# project-tsc.net
KiCad netlist of a schematic drawn in EAGLE
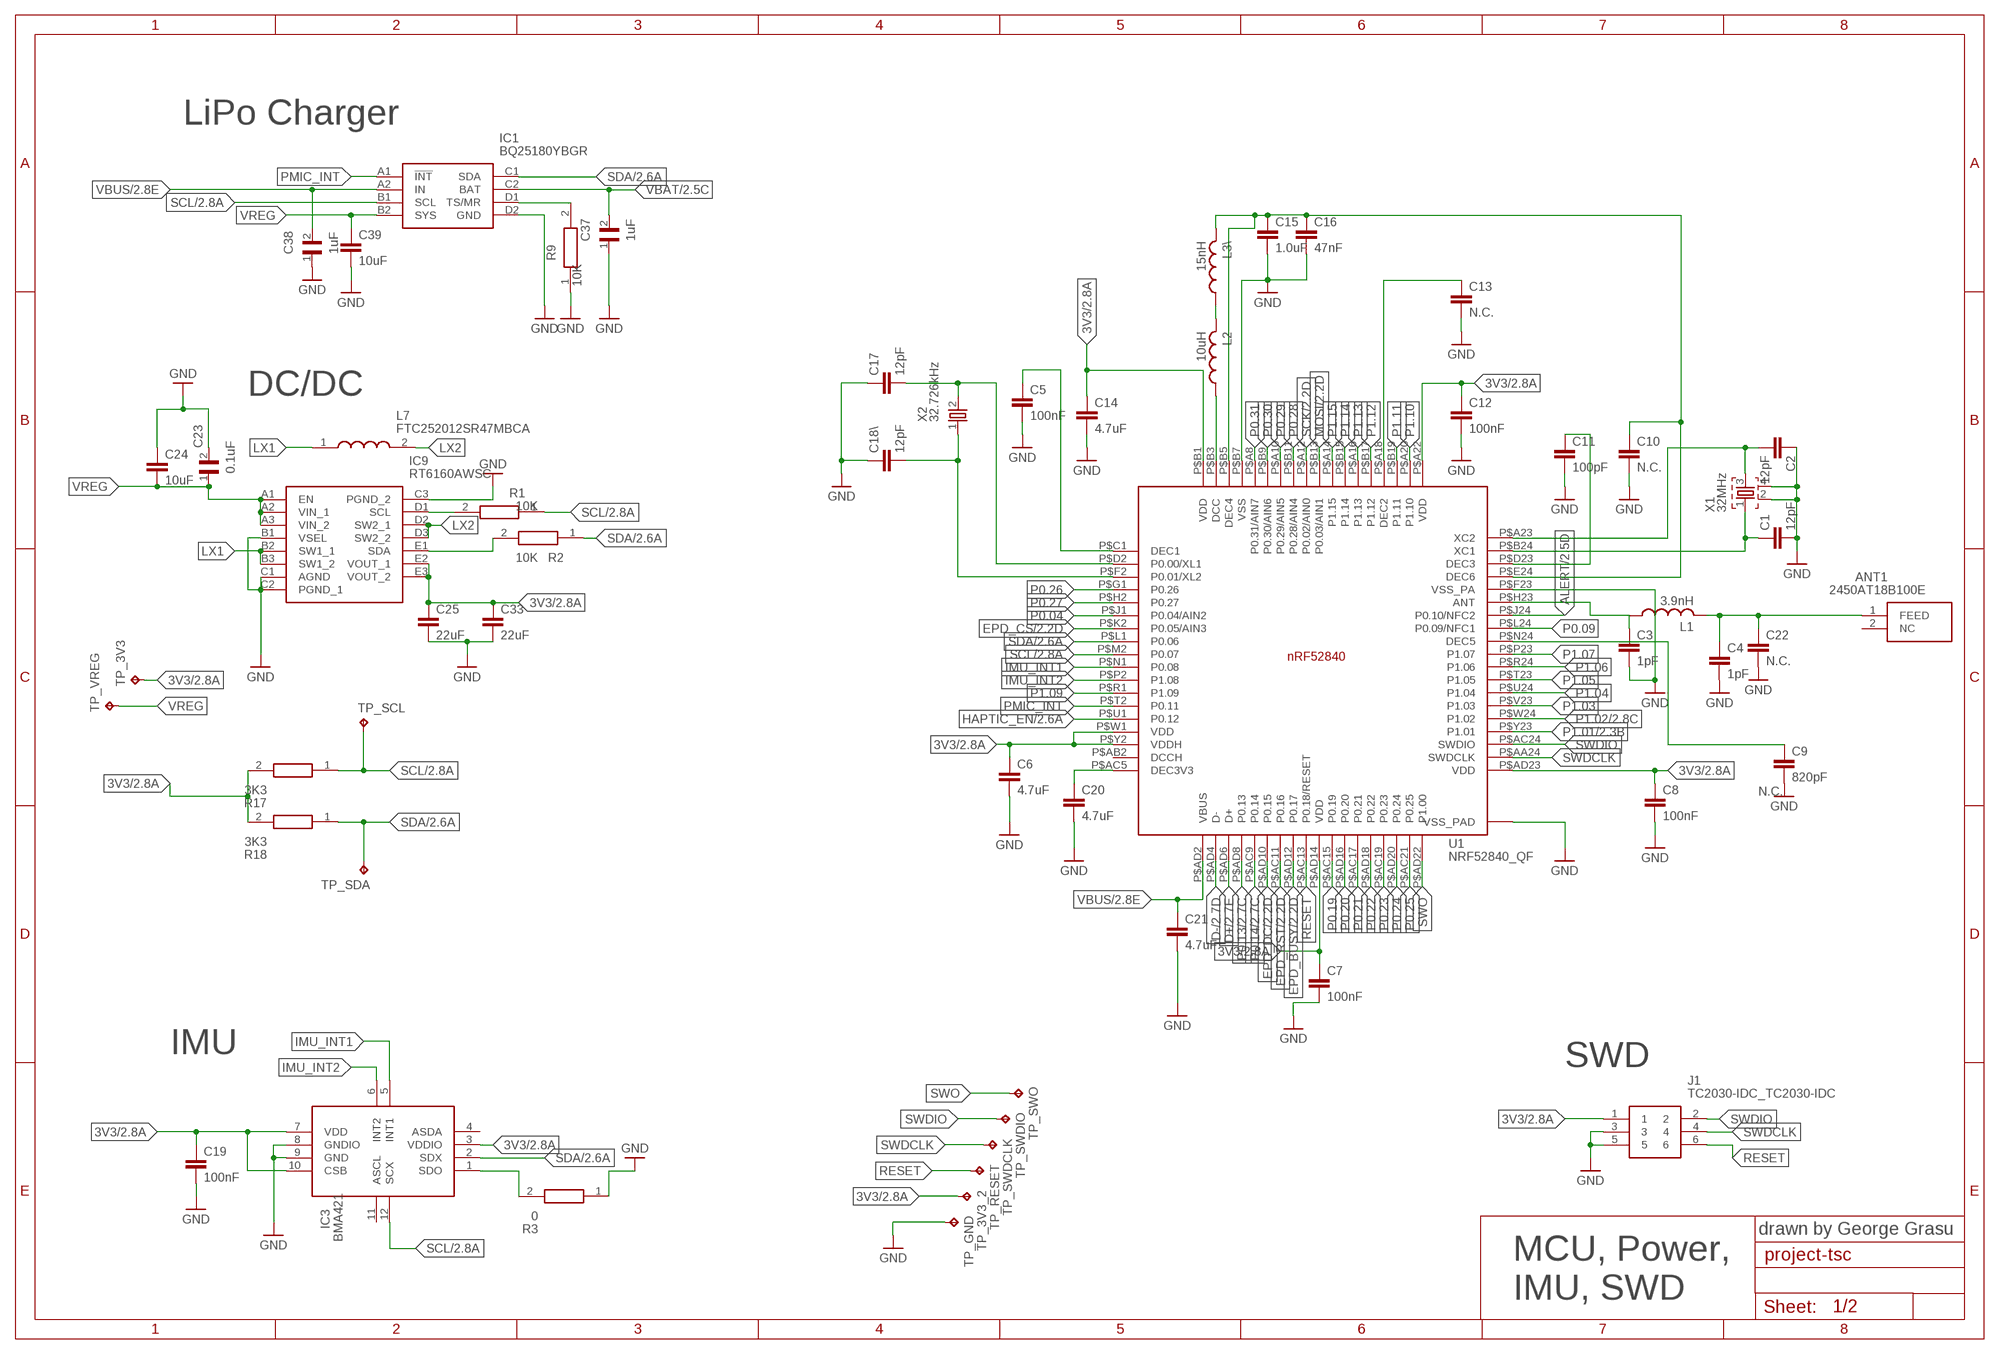
[diagram p0: schematic, sheet 1]
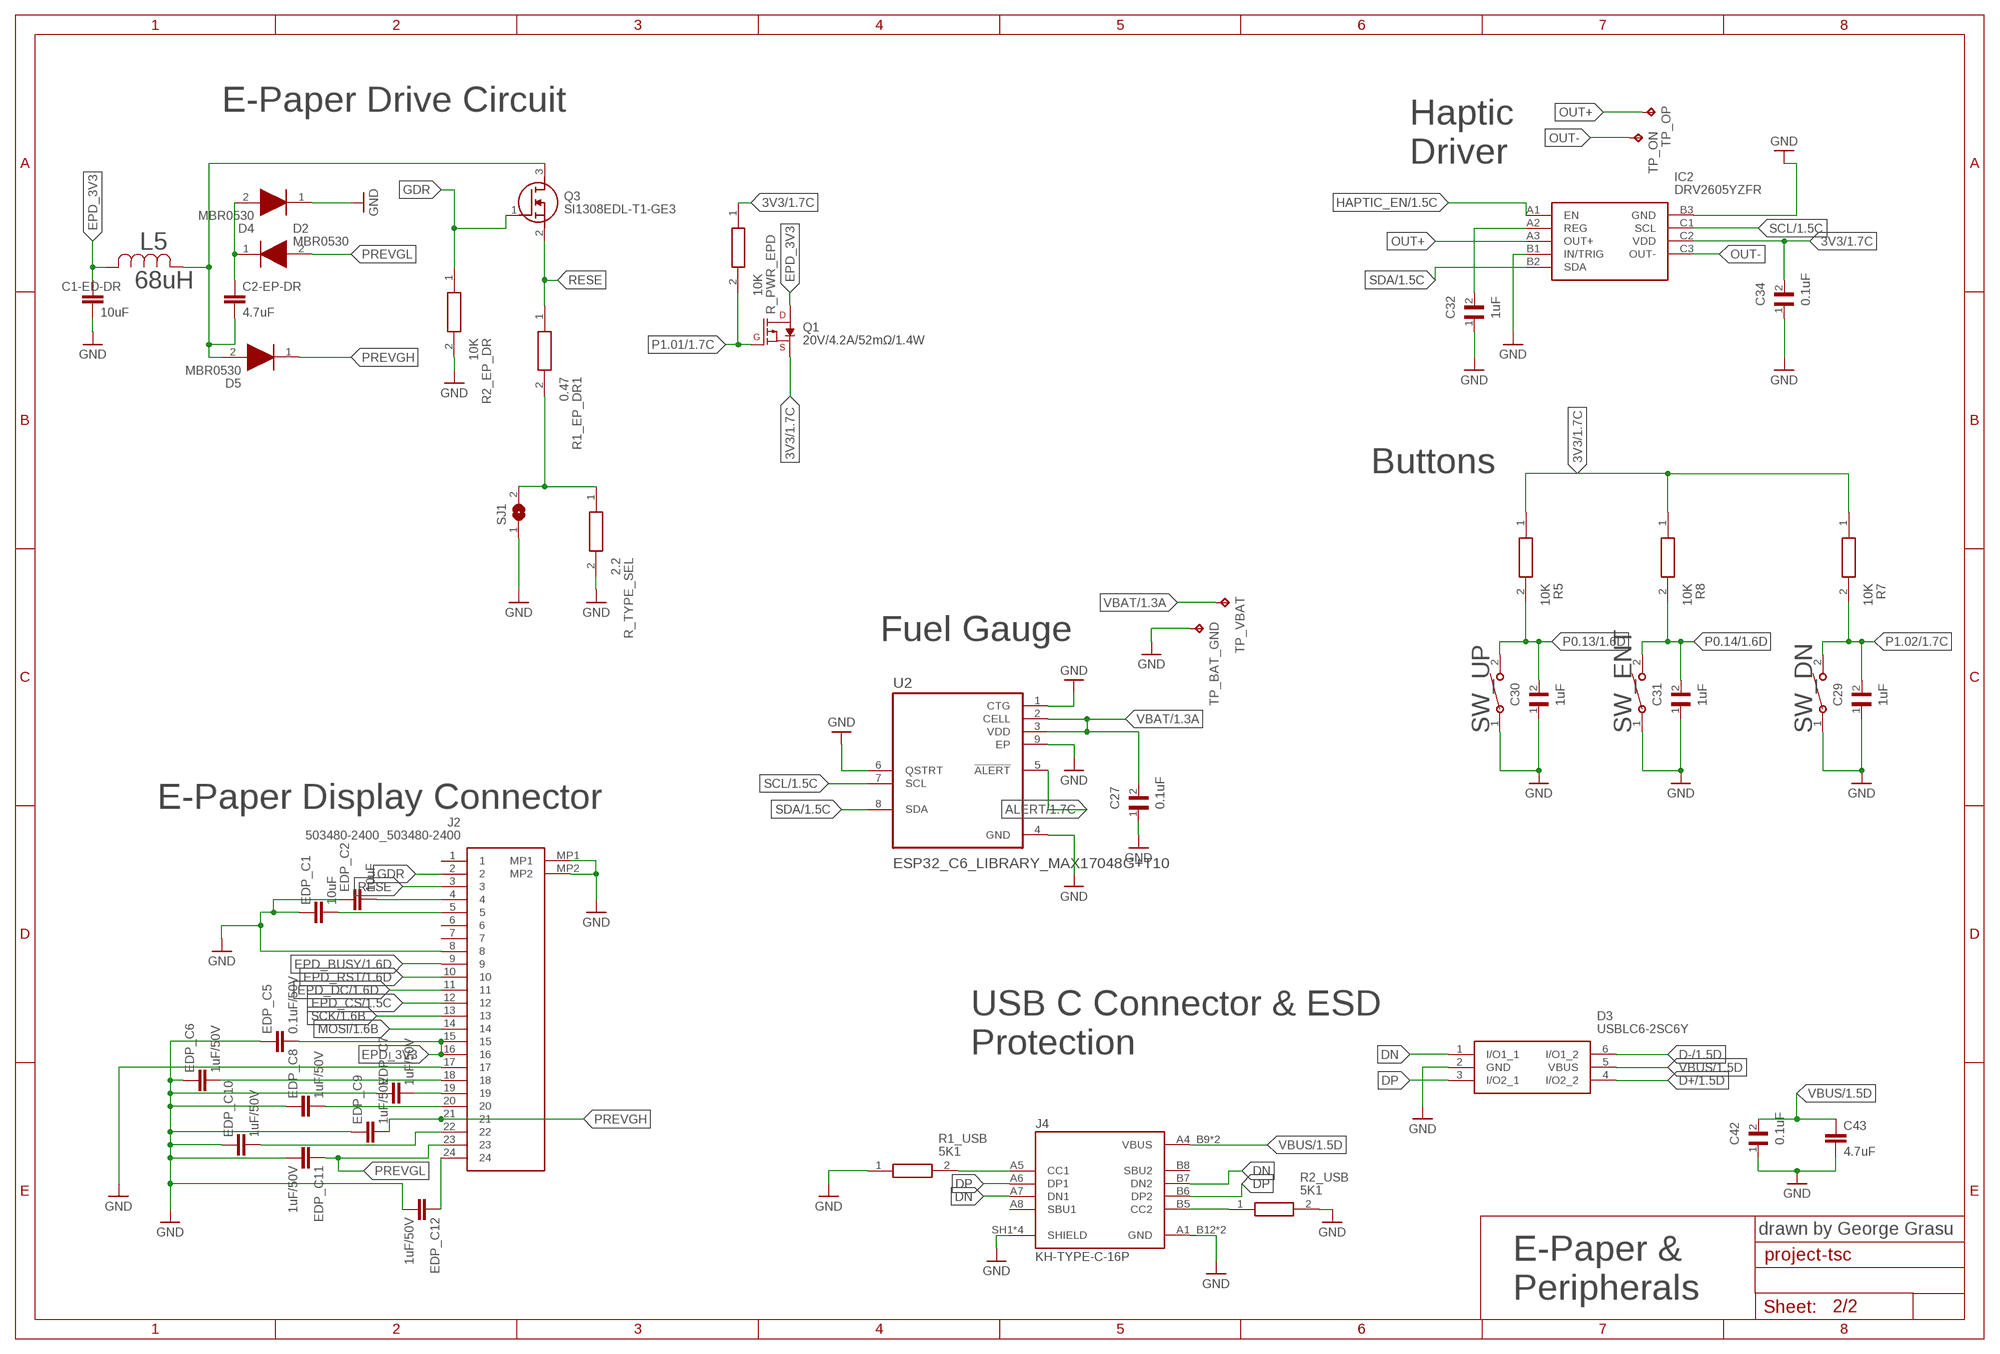
[diagram p1: schematic, sheet 2]

(export (version "E")
  (design (tool "Eeschema 10.0.6"))
  (components
    (comp (ref "ANT1")
      (value "2450AT18B100E")
      (footprint "eagle-import:2450AT18B100E_ANTC3216X140N")
      (fields (field (name "MOUSER_PART_NUMBER") "609-2450AT18B100E"))
      (libsource (lib "eagle-import") (part "2450AT18B100E_2450AT18B100E"))
    )
    (comp (ref "C1")
      (value "12pF")
      (footprint "eagle-import:NORDIC_NRF_3_RESC0201_L")
      (libsource (lib "eagle-import") (part "NORDIC_NRF_3_CAPACITOR_0201_L"))
    )
    (comp (ref "C2")
      (value "12pF")
      (footprint "eagle-import:NORDIC_NRF_3_RESC0201_L")
      (libsource (lib "eagle-import") (part "NORDIC_NRF_3_CAPACITOR_0201_L"))
    )
    (comp (ref "C3")
      (value "1pF")
      (footprint "eagle-import:NORDIC_NRF_3_RESC0201_N")
      (libsource (lib "eagle-import") (part "NORDIC_NRF_3_CAPACITOR_0201_N"))
    )
    (comp (ref "C4")
      (value "1pF")
      (footprint "eagle-import:NORDIC_NRF_3_RESC0201_N")
      (libsource (lib "eagle-import") (part "NORDIC_NRF_3_CAPACITOR_0201_N"))
    )
    (comp (ref "C5")
      (value "100nF")
      (footprint "eagle-import:NORDIC_NRF_3_RESC0201_L")
      (libsource (lib "eagle-import") (part "NORDIC_NRF_3_CAPACITOR_0201_L"))
    )
    (comp (ref "C6")
      (value "4.7uF")
      (footprint "eagle-import:NORDIC_NRF_3_RESC0402_N")
      (libsource (lib "eagle-import") (part "NORDIC_NRF_3_CAPACITOR_0402_N"))
    )
    (comp (ref "C7")
      (value "100nF")
      (footprint "eagle-import:NORDIC_NRF_3_RESC0201_N")
      (libsource (lib "eagle-import") (part "NORDIC_NRF_3_CAPACITOR_0201_N"))
    )
    (comp (ref "C8")
      (value "100nF")
      (footprint "eagle-import:NORDIC_NRF_3_RESC0201_N")
      (libsource (lib "eagle-import") (part "NORDIC_NRF_3_CAPACITOR_0201_N"))
    )
    (comp (ref "C9")
      (value "820pF")
      (footprint "eagle-import:NORDIC_NRF_3_RESC0201_N")
      (libsource (lib "eagle-import") (part "NORDIC_NRF_3_CAPACITOR_0201_N"))
    )
    (comp (ref "C10")
      (value "N.C.")
      (footprint "eagle-import:NORDIC_NRF_3_RESC0201_L")
      (libsource (lib "eagle-import") (part "NORDIC_NRF_3_CAPACITOR_0201_L"))
    )
    (comp (ref "C11")
      (value "100pF")
      (footprint "eagle-import:NORDIC_NRF_3_RESC0201_L")
      (libsource (lib "eagle-import") (part "NORDIC_NRF_3_CAPACITOR_0201_L"))
    )
    (comp (ref "C12")
      (value "100nF")
      (footprint "eagle-import:NORDIC_NRF_3_RESC0201_L")
      (libsource (lib "eagle-import") (part "NORDIC_NRF_3_CAPACITOR_0201_L"))
    )
    (comp (ref "C13")
      (value "N.C.")
      (footprint "eagle-import:NORDIC_NRF_3_RESC0201_L")
      (libsource (lib "eagle-import") (part "NORDIC_NRF_3_CAPACITOR_0201_L"))
    )
    (comp (ref "C14")
      (value "4.7uF")
      (footprint "eagle-import:NORDIC_NRF_3_RESC0201_L")
      (libsource (lib "eagle-import") (part "NORDIC_NRF_3_CAPACITOR_0201_L"))
    )
    (comp (ref "C15")
      (value "1.0uF")
      (footprint "eagle-import:NORDIC_NRF_3_RESC0201_L")
      (libsource (lib "eagle-import") (part "NORDIC_NRF_3_CAPACITOR_0201_L"))
    )
    (comp (ref "C16")
      (value "47nF")
      (footprint "eagle-import:NORDIC_NRF_3_RESC0201_L")
      (libsource (lib "eagle-import") (part "NORDIC_NRF_3_CAPACITOR_0201_L"))
    )
    (comp (ref "C17")
      (value "12pF")
      (footprint "eagle-import:NORDIC_NRF_3_RESC0201_L")
      (libsource (lib "eagle-import") (part "NORDIC_NRF_3_CAPACITOR_0201_L"))
    )
    (comp (ref "C18\\")
      (value "12pF")
      (footprint "eagle-import:NORDIC_NRF_3_RESC0201_L")
      (libsource (lib "eagle-import") (part "NORDIC_NRF_3_CAPACITOR_0201_L"))
    )
    (comp (ref "C19")
      (value "100nF")
      (footprint "eagle-import:NORDIC_NRF_3_RESC0201_L")
      (libsource (lib "eagle-import") (part "NORDIC_NRF_3_CAPACITOR_0201_L"))
    )
    (comp (ref "C20")
      (value "4.7uF")
      (footprint "eagle-import:NORDIC_NRF_3_RESC0402_N")
      (libsource (lib "eagle-import") (part "NORDIC_NRF_3_CAPACITOR_0402_N"))
    )
    (comp (ref "C21")
      (value "4.7uF")
      (footprint "eagle-import:NORDIC_NRF_3_RESC0402_N")
      (libsource (lib "eagle-import") (part "NORDIC_NRF_3_CAPACITOR_0402_N"))
    )
    (comp (ref "C22")
      (value "N.C.")
      (footprint "eagle-import:NORDIC_NRF_3_RESC0201_N")
      (libsource (lib "eagle-import") (part "NORDIC_NRF_3_CAPACITOR_0201_N"))
    )
    (comp (ref "C23")
      (value "0.1uF")
      (footprint "eagle-import:GRM011R60J152KE01L_2_CAPC0201X13N")
      (fields (field (name "MF") "Murata") (field (name "MP") "GRM011R60J152KE01L"))
      (libsource (lib "eagle-import") (part "GRM011R60J152KE01L_2_GRM011R60J152KE01L"))
    )
    (comp (ref "C24")
      (value "10uF")
      (footprint "eagle-import:NORDIC_NRF_3_RESC0201_L")
      (libsource (lib "eagle-import") (part "NORDIC_NRF_3_CAPACITOR_0201_L"))
    )
    (comp (ref "C25")
      (value "22uF")
      (footprint "eagle-import:NORDIC_NRF_3_RESC0201_L")
      (libsource (lib "eagle-import") (part "NORDIC_NRF_3_CAPACITOR_0201_L"))
    )
    (comp (ref "C33")
      (value "22uF")
      (footprint "eagle-import:NORDIC_NRF_3_RESC0201_L")
      (libsource (lib "eagle-import") (part "NORDIC_NRF_3_CAPACITOR_0201_L"))
    )
    (comp (ref "C37")
      (value "1uF")
      (footprint "eagle-import:GRM011R60J152KE01L_2_CAPC0201X13N")
      (fields (field (name "MF") "Murata") (field (name "MP") "GRM011R60J152KE01L"))
      (libsource (lib "eagle-import") (part "GRM011R60J152KE01L_2_GRM011R60J152KE01L"))
    )
    (comp (ref "C38")
      (value "1uF")
      (footprint "eagle-import:GRM011R60J152KE01L_2_CAPC0201X13N")
      (fields (field (name "MF") "Murata") (field (name "MP") "GRM011R60J152KE01L"))
      (libsource (lib "eagle-import") (part "GRM011R60J152KE01L_2_GRM011R60J152KE01L"))
    )
    (comp (ref "C39")
      (value "10uF")
      (footprint "eagle-import:NORDIC_NRF_3_RESC0201_L")
      (libsource (lib "eagle-import") (part "NORDIC_NRF_3_CAPACITOR_0201_L"))
    )
    (comp (ref "IC1")
      (value "BQ25180YBGR")
      (footprint "eagle-import:BQ25180YBGR_BGA8C40P2X4_100X155X50")
      (fields (field (name "MOUSER_PART_NUMBER") "595-BQ25180YBGR"))
      (libsource (lib "eagle-import") (part "BQ25180YBGR_BQ25180YBGR"))
    )
    (comp (ref "IC3")
      (value "BMA421")
      (footprint "eagle-import:BMA423_BMA423")
      (fields (field (name "ARROW_PART_NUMBER") "BMA423") (field (name "MOUSER_PART_NUMBER") "262-BMA423"))
      (libsource (lib "eagle-import") (part "BMA423_BMA423"))
    )
    (comp (ref "IC9")
      (value "RT6160AWSC")
      (footprint "eagle-import:RT6160AWSC_BGA15C40P3X5_140X230X60")
      (fields (field (name "MOUSER_PART_NUMBER") "835-RT6160AWSC"))
      (libsource (lib "eagle-import") (part "RT6160AWSC_RT6160AWSC"))
    )
    (comp (ref "J1")
      (value "TC2030-IDC_TC2030-IDC")
      (footprint "eagle-import:TC2030-IDC_TC2030IDC")
      (fields (field (name "MANUFACTURER_PART_NUMBER") "TC2030-IDC"))
      (libsource (lib "eagle-import") (part "TC2030-IDC_TC2030-IDC"))
    )
    (comp (ref "L1")
      (value "3.9nH")
      (footprint "eagle-import:NORDIC_NRF_2_RESC0402_L")
      (libsource (lib "eagle-import") (part "NORDIC_NRF_2_INDUCTOR_0402_L"))
    )
    (comp (ref "L2")
      (value "10uH")
      (footprint "eagle-import:NORDIC_NRF_2_RESC0402_L")
      (libsource (lib "eagle-import") (part "NORDIC_NRF_2_INDUCTOR_0402_L"))
    )
    (comp (ref "L3\\")
      (value "15nH")
      (footprint "eagle-import:NORDIC_NRF_2_RESC0402_L")
      (libsource (lib "eagle-import") (part "NORDIC_NRF_2_INDUCTOR_0402_L"))
    )
    (comp (ref "L7")
      (value "FTC252012SR47MBCA")
      (footprint "eagle-import:MLP2016SR47MT0S1_INDC2016X100N")
      (libsource (lib "eagle-import") (part "MLP2016SR47MT0S1_FTC252012SR47MBCA"))
    )
    (comp (ref "R1")
      (value "10K")
      (footprint "eagle-import:CPF0201D7K68C1_0201")
      (libsource (lib "eagle-import") (part "CPF0201D7K68C1_CPF0201D7K68C1"))
    )
    (comp (ref "R2")
      (value "10K")
      (footprint "eagle-import:CPF0201D7K68C1_0201")
      (libsource (lib "eagle-import") (part "CPF0201D7K68C1_CPF0201D7K68C1"))
    )
    (comp (ref "R3")
      (value "0")
      (footprint "eagle-import:CPF0201D7K68C1_0201")
      (libsource (lib "eagle-import") (part "CPF0201D7K68C1_CPF0201D7K68C1"))
    )
    (comp (ref "R9")
      (value "10K")
      (footprint "eagle-import:CPF0201D7K68C1_0201")
      (libsource (lib "eagle-import") (part "CPF0201D7K68C1_CPF0201D7K68C1"))
    )
    (comp (ref "R17")
      (value "3K3")
      (footprint "eagle-import:CPF0201D7K68C1_0201")
      (libsource (lib "eagle-import") (part "CPF0201D7K68C1_CPF0201D7K68C1"))
    )
    (comp (ref "R18")
      (value "3K3")
      (footprint "eagle-import:CPF0201D7K68C1_0201")
      (libsource (lib "eagle-import") (part "CPF0201D7K68C1_CPF0201D7K68C1"))
    )
    (comp (ref "TP_3V3")
      (value "HECTOR_WATCH_1_TPTP20R")
      (footprint "eagle-import:HECTOR_WATCH_1_TP20R")
      (libsource (lib "eagle-import") (part "HECTOR_WATCH_1_TPTP20R"))
    )
    (comp (ref "TP_3V3_2")
      (value "HECTOR_WATCH_1_TPTP20R")
      (footprint "eagle-import:HECTOR_WATCH_1_TP20R")
      (libsource (lib "eagle-import") (part "HECTOR_WATCH_1_TPTP20R"))
    )
    (comp (ref "TP_GND")
      (value "HECTOR_WATCH_1_TPTP20R")
      (footprint "eagle-import:HECTOR_WATCH_1_TP20R")
      (libsource (lib "eagle-import") (part "HECTOR_WATCH_1_TPTP20R"))
    )
    (comp (ref "TP_RESET")
      (value "HECTOR_WATCH_1_TPTP20R")
      (footprint "eagle-import:HECTOR_WATCH_1_TP20R")
      (libsource (lib "eagle-import") (part "HECTOR_WATCH_1_TPTP20R"))
    )
    (comp (ref "TP_SCL")
      (value "HECTOR_WATCH_1_TPTP20R")
      (footprint "eagle-import:HECTOR_WATCH_1_TP20R")
      (libsource (lib "eagle-import") (part "HECTOR_WATCH_1_TPTP20R"))
    )
    (comp (ref "TP_SDA")
      (value "HECTOR_WATCH_1_TPTP20R")
      (footprint "eagle-import:HECTOR_WATCH_1_TP20R")
      (libsource (lib "eagle-import") (part "HECTOR_WATCH_1_TPTP20R"))
    )
    (comp (ref "TP_SWDCLK")
      (value "HECTOR_WATCH_1_TPTP20R")
      (footprint "eagle-import:HECTOR_WATCH_1_TP20R")
      (libsource (lib "eagle-import") (part "HECTOR_WATCH_1_TPTP20R"))
    )
    (comp (ref "TP_SWDIO")
      (value "HECTOR_WATCH_1_TPTP20R")
      (footprint "eagle-import:HECTOR_WATCH_1_TP20R")
      (libsource (lib "eagle-import") (part "HECTOR_WATCH_1_TPTP20R"))
    )
    (comp (ref "TP_SWO")
      (value "HECTOR_WATCH_1_TPTP20R")
      (footprint "eagle-import:HECTOR_WATCH_1_TP20R")
      (libsource (lib "eagle-import") (part "HECTOR_WATCH_1_TPTP20R"))
    )
    (comp (ref "TP_VREG")
      (value "HECTOR_WATCH_1_TPTP20R")
      (footprint "eagle-import:HECTOR_WATCH_1_TP20R")
      (libsource (lib "eagle-import") (part "HECTOR_WATCH_1_TPTP20R"))
    )
    (comp (ref "U1")
      (value "NRF52840_QF")
      (footprint "eagle-import:NORDIC_NRF_4_AQFN50P700X700X85_HS-74N")
      (libsource (lib "eagle-import") (part "NORDIC_NRF_4_NRF52840_QF"))
    )
    (comp (ref "X1")
      (value "32MHz")
      (footprint "eagle-import:NORDIC_NRF_BT-XTAL_2016_N")
      (libsource (lib "eagle-import") (part "NORDIC_NRF_XTAL_32MHZ"))
    )
    (comp (ref "X2")
      (value "32.726kHz")
      (footprint "eagle-import:NORDIC_NRF_1_XTAL_3215_N")
      (libsource (lib "eagle-import") (part "NORDIC_NRF_1_XTAL_32KHZ"))
    )
    (comp (ref "C1-ED-DR")
      (value "10uF")
      (footprint "eagle-import:NORDIC_NRF_3_RESC0402_N")
      (libsource (lib "eagle-import") (part "NORDIC_NRF_3_CAPACITOR_0402_N"))
    )
    (comp (ref "C2-EP-DR")
      (value "4.7uF")
      (footprint "eagle-import:NORDIC_NRF_3_RESC0402_N")
      (libsource (lib "eagle-import") (part "NORDIC_NRF_3_CAPACITOR_0402_N"))
    )
    (comp (ref "C27")
      (value "0.1uF")
      (footprint "eagle-import:GRM011R60J152KE01L_2_CAPC0201X13N")
      (fields (field (name "MF") "Murata") (field (name "MP") "GRM011R60J152KE01L"))
      (libsource (lib "eagle-import") (part "GRM011R60J152KE01L_2_GRM011R60J152KE01L"))
    )
    (comp (ref "C29")
      (value "1uF")
      (footprint "eagle-import:GRM011R60J152KE01L_2_CAPC0201X13N")
      (fields (field (name "MF") "Murata") (field (name "MP") "GRM011R60J152KE01L"))
      (libsource (lib "eagle-import") (part "GRM011R60J152KE01L_2_GRM011R60J152KE01L"))
    )
    (comp (ref "C30")
      (value "1uF")
      (footprint "eagle-import:GRM011R60J152KE01L_2_CAPC0201X13N")
      (fields (field (name "MF") "Murata") (field (name "MP") "GRM011R60J152KE01L"))
      (libsource (lib "eagle-import") (part "GRM011R60J152KE01L_2_GRM011R60J152KE01L"))
    )
    (comp (ref "C31")
      (value "1uF")
      (footprint "eagle-import:GRM011R60J152KE01L_2_CAPC0201X13N")
      (fields (field (name "MF") "Murata") (field (name "MP") "GRM011R60J152KE01L"))
      (libsource (lib "eagle-import") (part "GRM011R60J152KE01L_2_GRM011R60J152KE01L"))
    )
    (comp (ref "C32")
      (value "1uF")
      (footprint "eagle-import:GRM011R60J152KE01L_2_CAPC0201X13N")
      (fields (field (name "MF") "Murata") (field (name "MP") "GRM011R60J152KE01L"))
      (libsource (lib "eagle-import") (part "GRM011R60J152KE01L_2_GRM011R60J152KE01L"))
    )
    (comp (ref "C34")
      (value "0.1uF")
      (footprint "eagle-import:GRM011R60J152KE01L_2_CAPC0201X13N")
      (fields (field (name "MF") "Murata") (field (name "MP") "GRM011R60J152KE01L"))
      (libsource (lib "eagle-import") (part "GRM011R60J152KE01L_2_GRM011R60J152KE01L"))
    )
    (comp (ref "C42")
      (value "0.1uF")
      (footprint "eagle-import:GRM011R60J152KE01L_2_CAPC0201X13N")
      (fields (field (name "MF") "Murata") (field (name "MP") "GRM011R60J152KE01L"))
      (libsource (lib "eagle-import") (part "GRM011R60J152KE01L_2_GRM011R60J152KE01L"))
    )
    (comp (ref "C43")
      (value "4.7uF")
      (footprint "eagle-import:NORDIC_NRF_3_RESC0201_L")
      (libsource (lib "eagle-import") (part "NORDIC_NRF_3_CAPACITOR_0201_L"))
    )
    (comp (ref "D2")
      (value "MBR0530")
      (footprint "eagle-import:ESP32_C6_LIBRARY_5_SOD3716X135N")
      (fields (field (name "MF") "ON Semiconductor"))
      (libsource (lib "eagle-import") (part "ESP32_C6_LIBRARY_5_MBR0530"))
    )
    (comp (ref "D3")
      (value "USBLC6-2SC6Y")
      (footprint "eagle-import:ESP32_C6_LIBRARY_3_SOT95P280X145-6N")
      (fields (field (name "MF") "STMicroelectronics"))
      (libsource (lib "eagle-import") (part "ESP32_C6_LIBRARY_3_USBLC6-2SC6Y"))
    )
    (comp (ref "D4")
      (value "MBR0530")
      (footprint "eagle-import:ESP32_C6_LIBRARY_5_SOD3716X135N")
      (fields (field (name "MF") "ON Semiconductor"))
      (libsource (lib "eagle-import") (part "ESP32_C6_LIBRARY_5_MBR0530"))
    )
    (comp (ref "D5")
      (value "MBR0530")
      (footprint "eagle-import:ESP32_C6_LIBRARY_5_SOD3716X135N")
      (fields (field (name "MF") "ON Semiconductor"))
      (libsource (lib "eagle-import") (part "ESP32_C6_LIBRARY_5_MBR0530"))
    )
    (comp (ref "EDP_C1")
      (value "10uF")
      (footprint "eagle-import:NORDIC_NRF_3_RESC0201_L")
      (libsource (lib "eagle-import") (part "NORDIC_NRF_3_CAPACITOR_0201_L"))
    )
    (comp (ref "EDP_C2")
      (value "10uF")
      (footprint "eagle-import:NORDIC_NRF_3_RESC0201_L")
      (libsource (lib "eagle-import") (part "NORDIC_NRF_3_CAPACITOR_0201_L"))
    )
    (comp (ref "EDP_C5")
      (value "0.1uF/50V")
      (footprint "eagle-import:NORDIC_NRF_3_RESC0201_L")
      (libsource (lib "eagle-import") (part "NORDIC_NRF_3_CAPACITOR_0201_L"))
    )
    (comp (ref "EDP_C6")
      (value "1uF/50V")
      (footprint "eagle-import:NORDIC_NRF_3_RESC0201_L")
      (libsource (lib "eagle-import") (part "NORDIC_NRF_3_CAPACITOR_0201_L"))
    )
    (comp (ref "EDP_C7")
      (value "1uF/50V")
      (footprint "eagle-import:NORDIC_NRF_3_RESC0201_L")
      (libsource (lib "eagle-import") (part "NORDIC_NRF_3_CAPACITOR_0201_L"))
    )
    (comp (ref "EDP_C8")
      (value "1uF/50V")
      (footprint "eagle-import:NORDIC_NRF_3_RESC0201_L")
      (libsource (lib "eagle-import") (part "NORDIC_NRF_3_CAPACITOR_0201_L"))
    )
    (comp (ref "EDP_C9")
      (value "1uF/50V")
      (footprint "eagle-import:NORDIC_NRF_3_RESC0201_L")
      (libsource (lib "eagle-import") (part "NORDIC_NRF_3_CAPACITOR_0201_L"))
    )
    (comp (ref "EDP_C10")
      (value "1uF/50V")
      (footprint "eagle-import:NORDIC_NRF_3_RESC0201_L")
      (libsource (lib "eagle-import") (part "NORDIC_NRF_3_CAPACITOR_0201_L"))
    )
    (comp (ref "EDP_C11")
      (value "1uF/50V")
      (footprint "eagle-import:NORDIC_NRF_3_RESC0201_L")
      (libsource (lib "eagle-import") (part "NORDIC_NRF_3_CAPACITOR_0201_L"))
    )
    (comp (ref "EDP_C12")
      (value "1uF/50V")
      (footprint "eagle-import:NORDIC_NRF_3_RESC0201_L")
      (libsource (lib "eagle-import") (part "NORDIC_NRF_3_CAPACITOR_0201_L"))
    )
    (comp (ref "IC2")
      (value "DRV2605YZFR")
      (footprint "eagle-import:DRV2605YZFR_BGA9C50P3X3_144X144X62")
      (libsource (lib "eagle-import") (part "DRV2605YZFR_DRV2605YZFR"))
    )
    (comp (ref "J2")
      (value "503480-2400_503480-2400")
      (footprint "eagle-import:503480-2400_5034802400")
      (fields
        (field (name "MANUFACTURER_PART_NUMBER") "503480-2400")
        (field (name "MOUSER_PART_NUMBER") "538-503480-2400")
      )
      (libsource (lib "eagle-import") (part "503480-2400_503480-2400"))
    )
    (comp (ref "J4")
      (value "KH-TYPE-C-16P")
      (footprint "eagle-import:KH-TYPE-C-16P_KINGHELM_KH-TYPE-C-16P")
      (fields (field (name "MF") "kinghelm"))
      (libsource (lib "eagle-import") (part "KH-TYPE-C-16P_KH-TYPE-C-16P"))
    )
    (comp (ref "L5")
      (value "68uH")
      (footprint "eagle-import:ESP32_C6_LIBRARY_2_IND_4828-WE-TPC_WRE")
      (fields
        (field (name "MANUFACTURER_PART_NUMBER") "744043680")
        (field (name "COPYRIGHT") "Copyright (C) 2024 Ultra Librarian. All rights reserved.")
      )
      (libsource (lib "eagle-import") (part "ESP32_C6_LIBRARY_2_744043680IND_4828-WE-TPC_WRE"))
    )
    (comp (ref "Q1")
      (value "20V/4.2A/52mΩ/1.4W")
      (footprint "eagle-import:ESP32_C6_LIBRARY_4_ESP32_C6_LIBRARY_4_ESP32_C6_LIBRARY_4_ESP32_C6_LIBRARY_4_ESP32_WROVER_SPARKFUN-DISCRETESEMI_SOT23-3")
      (libsource (lib "eagle-import") (part "ESP32_C6_LIBRARY_4_ESP32_WROVER_SPARKFUN-DISCRETESEMI_MOSFET_PCH-DMG2305UX-7"))
    )
    (comp (ref "Q3")
      (value "SI1308EDL-T1-GE3")
      (footprint "eagle-import:ESP32_C6_LIBRARY_6_SOT65P210X110-3N")
      (fields (field (name "MF") "Vishay Siliconix"))
      (libsource (lib "eagle-import") (part "ESP32_C6_LIBRARY_6_SI1308EDL-T1-GE3"))
    )
    (comp (ref "R1_EP_DR1")
      (value "0.47")
      (footprint "eagle-import:CPF0201D7K68C1_0201")
      (libsource (lib "eagle-import") (part "CPF0201D7K68C1_CPF0201D7K68C1"))
    )
    (comp (ref "R1_USB")
      (value "5K1")
      (footprint "eagle-import:CPF0201D7K68C1_0201")
      (libsource (lib "eagle-import") (part "CPF0201D7K68C1_CPF0201D7K68C1"))
    )
    (comp (ref "R2_EP_DR")
      (value "10K")
      (footprint "eagle-import:CPF0201D7K68C1_0201")
      (libsource (lib "eagle-import") (part "CPF0201D7K68C1_CPF0201D7K68C1"))
    )
    (comp (ref "R2_USB")
      (value "5K1")
      (footprint "eagle-import:CPF0201D7K68C1_0201")
      (libsource (lib "eagle-import") (part "CPF0201D7K68C1_CPF0201D7K68C1"))
    )
    (comp (ref "R5")
      (value "10K")
      (footprint "eagle-import:CPF0201D7K68C1_0201")
      (libsource (lib "eagle-import") (part "CPF0201D7K68C1_CPF0201D7K68C1"))
    )
    (comp (ref "R7")
      (value "10K")
      (footprint "eagle-import:CPF0201D7K68C1_0201")
      (libsource (lib "eagle-import") (part "CPF0201D7K68C1_CPF0201D7K68C1"))
    )
    (comp (ref "R8")
      (value "10K")
      (footprint "eagle-import:CPF0201D7K68C1_0201")
      (libsource (lib "eagle-import") (part "CPF0201D7K68C1_CPF0201D7K68C1"))
    )
    (comp (ref "R_PWR_EPD")
      (value "10K")
      (footprint "eagle-import:CPF0201D7K68C1_0201")
      (libsource (lib "eagle-import") (part "CPF0201D7K68C1_CPF0201D7K68C1"))
    )
    (comp (ref "R_TYPE_SEL")
      (value "2.2")
      (footprint "eagle-import:CPF0201D7K68C1_0201")
      (libsource (lib "eagle-import") (part "CPF0201D7K68C1_CPF0201D7K68C1"))
    )
    (comp (ref "SJ1")
      (value "ESP32_C6_LIBRARY_7_JUMPER_SJ")
      (footprint "eagle-import:ESP32_C6_LIBRARY_7_JUMPER_SJ")
      (libsource (lib "eagle-import") (part "ESP32_C6_LIBRARY_7_JUMPER_SJ"))
    )
    (comp (ref "SW_DN")
      (value "2025-10-22_07-23-44_LIBRARY_EVP-AKE31ASW_EVP-AKE31A_PAN")
      (footprint "eagle-import:2025-10-22_07-23-44_LIBRARY_SW_EVP-AKE31A_PAN")
      (fields
        (field (name "MANUFACTURER_PART_NUMBER") "EVP-AKE31A")
        (field (name "COPYRIGHT") "Copyright (C) 2025 Ultra Librarian. All rights reserved.")
      )
      (libsource (lib "eagle-import") (part "2025-10-22_07-23-44_LIBRARY_EVP-AKE31ASW_EVP-AKE31A_PAN"))
    )
    (comp (ref "SW_ENT")
      (value "2025-10-22_07-23-44_LIBRARY_EVP-AKE31ASW_EVP-AKE31A_PAN")
      (footprint "eagle-import:2025-10-22_07-23-44_LIBRARY_SW_EVP-AKE31A_PAN")
      (fields
        (field (name "MANUFACTURER_PART_NUMBER") "EVP-AKE31A")
        (field (name "COPYRIGHT") "Copyright (C) 2025 Ultra Librarian. All rights reserved.")
      )
      (libsource (lib "eagle-import") (part "2025-10-22_07-23-44_LIBRARY_EVP-AKE31ASW_EVP-AKE31A_PAN"))
    )
    (comp (ref "SW_UP")
      (value "2025-10-22_07-23-44_LIBRARY_EVP-AKE31ASW_EVP-AKE31A_PAN")
      (footprint "eagle-import:2025-10-22_07-23-44_LIBRARY_SW_EVP-AKE31A_PAN")
      (fields
        (field (name "MANUFACTURER_PART_NUMBER") "EVP-AKE31A")
        (field (name "COPYRIGHT") "Copyright (C) 2025 Ultra Librarian. All rights reserved.")
      )
      (libsource (lib "eagle-import") (part "2025-10-22_07-23-44_LIBRARY_EVP-AKE31ASW_EVP-AKE31A_PAN"))
    )
    (comp (ref "TP_BAT_GND")
      (value "HECTOR_WATCH_1_TPTP20R")
      (footprint "eagle-import:HECTOR_WATCH_1_TP20R")
      (libsource (lib "eagle-import") (part "HECTOR_WATCH_1_TPTP20R"))
    )
    (comp (ref "TP_ON")
      (value "HECTOR_WATCH_1_TPTP20R")
      (footprint "eagle-import:HECTOR_WATCH_1_TP20R")
      (libsource (lib "eagle-import") (part "HECTOR_WATCH_1_TPTP20R"))
    )
    (comp (ref "TP_OP")
      (value "HECTOR_WATCH_1_TPTP20R")
      (footprint "eagle-import:HECTOR_WATCH_1_TP20R")
      (libsource (lib "eagle-import") (part "HECTOR_WATCH_1_TPTP20R"))
    )
    (comp (ref "TP_VBAT")
      (value "HECTOR_WATCH_1_TPTP20R")
      (footprint "eagle-import:HECTOR_WATCH_1_TP20R")
      (libsource (lib "eagle-import") (part "HECTOR_WATCH_1_TPTP20R"))
    )
    (comp (ref "U2")
      (value "ESP32_C6_LIBRARY_MAX17048G+T10")
      (footprint "eagle-import:ESP32_C6_LIBRARY_SON50P200X200X80-9N")
      (fields (field (name "MF") "Analog Devices") (field (name "MP") "MAX17048G+T10"))
      (libsource (lib "eagle-import") (part "ESP32_C6_LIBRARY_MAX17048G+T10"))
    )
  )
  (nets
    (net (code "1") (name "3V3") (class "Default")
      (node (ref "C12") (pin "1") (pinfunction "1_1") (pintype "passive"))
      (node (ref "C14") (pin "1") (pinfunction "1_1") (pintype "passive"))
      (node (ref "C19") (pin "1") (pinfunction "1_1") (pintype "passive"))
      (node (ref "C25") (pin "1") (pinfunction "1_1") (pintype "passive"))
      (node (ref "C33") (pin "1") (pinfunction "1_1") (pintype "passive"))
      (node (ref "C34") (pin "2") (pinfunction "2_2") (pintype "passive"))
      (node (ref "C6") (pin "1") (pinfunction "1_1") (pintype "passive"))
      (node (ref "C7") (pin "1") (pinfunction "1_1") (pintype "passive"))
      (node (ref "C8") (pin "1") (pinfunction "1_1") (pintype "passive"))
      (node (ref "IC2") (pin "C2") (pinfunction "VDD_C2") (pintype "bidirectional"))
      (node (ref "IC3") (pin "10") (pinfunction "CSB_10") (pintype "bidirectional"))
      (node (ref "IC3") (pin "3") (pinfunction "VDDIO_3") (pintype "bidirectional"))
      (node (ref "IC3") (pin "7") (pinfunction "VDD_7") (pintype "bidirectional"))
      (node (ref "IC9") (pin "E2") (pinfunction "VOUT_1_E2") (pintype "bidirectional"))
      (node (ref "IC9") (pin "E3") (pinfunction "VOUT_2_E3") (pintype "bidirectional"))
      (node (ref "J1") (pin "1") (pinfunction "1_1") (pintype "bidirectional"))
      (node (ref "Q1") (pin "2") (pinfunction "S_2") (pintype "bidirectional"))
      (node (ref "R17") (pin "2") (pinfunction "2_2") (pintype "bidirectional"))
      (node (ref "R18") (pin "2") (pinfunction "2_2") (pintype "bidirectional"))
      (node (ref "R5") (pin "1") (pinfunction "1_1") (pintype "bidirectional"))
      (node (ref "R7") (pin "1") (pinfunction "1_1") (pintype "bidirectional"))
      (node (ref "R8") (pin "1") (pinfunction "1_1") (pintype "bidirectional"))
      (node (ref "R_PWR_EPD") (pin "1") (pinfunction "1_1") (pintype "bidirectional"))
      (node (ref "TP_3V3") (pin "TP") (pinfunction "TP_TP") (pintype "input"))
      (node (ref "TP_3V3_2") (pin "TP") (pinfunction "TP_TP") (pintype "input"))
      (node (ref "U1") (pin "P$A22") (pinfunction "VDD_P$A22") (pintype "power_in"))
      (node (ref "U1") (pin "P$AD14") (pinfunction "VDD_P$AD14") (pintype "power_in"))
      (node (ref "U1") (pin "P$AD23") (pinfunction "VDD_P$AD23") (pintype "power_in"))
      (node (ref "U1") (pin "P$B1") (pinfunction "VDD_P$B1") (pintype "power_in"))
      (node (ref "U1") (pin "P$W1") (pinfunction "VDD_P$W1") (pintype "power_in"))
      (node (ref "U1") (pin "P$Y2") (pinfunction "VDDH_P$Y2") (pintype "power_in"))
    )
    (net (code "2") (name "ALERT") (class "Default")
      (node (ref "U1") (pin "P$J24") (pinfunction "P0.10/NFC2_P$J24") (pintype "bidirectional"))
      (node (ref "U2") (pin "5") (pinfunction "~{ALERT}_5") (pintype "output"))
    )
    (net (code "3") (name "D+") (class "Default")
      (node (ref "D3") (pin "4") (pinfunction "I/O2_2_4") (pintype "bidirectional"))
      (node (ref "U1") (pin "P$AD6") (pinfunction "D+_P$AD6") (pintype "bidirectional"))
    )
    (net (code "4") (name "D-") (class "Default")
      (node (ref "D3") (pin "6") (pinfunction "I/O1_2_6") (pintype "bidirectional"))
      (node (ref "U1") (pin "P$AD4") (pinfunction "D-_P$AD4") (pintype "bidirectional"))
    )
    (net (code "5") (name "DN") (class "Default")
      (node (ref "D3") (pin "1") (pinfunction "I/O1_1_1") (pintype "bidirectional"))
      (node (ref "J4") (pin "A7") (pinfunction "DN1_A7") (pintype "bidirectional"))
      (node (ref "J4") (pin "B7") (pinfunction "DN2_B7") (pintype "bidirectional"))
    )
    (net (code "6") (name "DP") (class "Default")
      (node (ref "D3") (pin "3") (pinfunction "I/O2_1_3") (pintype "bidirectional"))
      (node (ref "J4") (pin "A6") (pinfunction "DP1_A6") (pintype "bidirectional"))
      (node (ref "J4") (pin "B6") (pinfunction "DP2_B6") (pintype "bidirectional"))
    )
    (net (code "7") (name "EPD_3V3") (class "Default")
      (node (ref "C1-ED-DR") (pin "1") (pinfunction "1_1") (pintype "passive"))
      (node (ref "EDP_C5") (pin "2") (pinfunction "2_2") (pintype "passive"))
      (node (ref "J2") (pin "15") (pinfunction "15_15") (pintype "bidirectional"))
      (node (ref "J2") (pin "16") (pinfunction "16_16") (pintype "bidirectional"))
      (node (ref "L5") (pin "2") (pinfunction "2_2") (pintype "passive"))
      (node (ref "Q1") (pin "3") (pinfunction "D_3") (pintype "bidirectional"))
    )
    (net (code "8") (name "EPD_BUSY") (class "Default")
      (node (ref "J2") (pin "9") (pinfunction "9_9") (pintype "bidirectional"))
      (node (ref "U1") (pin "P$AD12") (pinfunction "P0.17_P$AD12") (pintype "bidirectional"))
    )
    (net (code "9") (name "EPD_CS") (class "Default")
      (node (ref "J2") (pin "12") (pinfunction "12_12") (pintype "bidirectional"))
      (node (ref "U1") (pin "P$K2") (pinfunction "P0.05/AIN3_P$K2") (pintype "bidirectional"))
    )
    (net (code "10") (name "EPD_DC") (class "Default")
      (node (ref "J2") (pin "11") (pinfunction "11_11") (pintype "bidirectional"))
      (node (ref "U1") (pin "P$AD10") (pinfunction "P0.15_P$AD10") (pintype "bidirectional"))
    )
    (net (code "11") (name "EPD_RST") (class "Default")
      (node (ref "J2") (pin "10") (pinfunction "10_10") (pintype "bidirectional"))
      (node (ref "U1") (pin "P$AC11") (pinfunction "P0.16_P$AC11") (pintype "bidirectional"))
    )
    (net (code "12") (name "GDR") (class "Default")
      (node (ref "J2") (pin "2") (pinfunction "2_2") (pintype "bidirectional"))
      (node (ref "Q3") (pin "1") (pinfunction "G_1") (pintype "bidirectional"))
      (node (ref "R2_EP_DR") (pin "1") (pinfunction "1_1") (pintype "bidirectional"))
    )
    (net (code "13") (name "GND") (class "Default")
      (node (ref "C1") (pin "2") (pinfunction "2_2") (pintype "passive"))
      (node (ref "C1-ED-DR") (pin "2") (pinfunction "2_2") (pintype "passive"))
      (node (ref "C10") (pin "2") (pinfunction "2_2") (pintype "passive"))
      (node (ref "C11") (pin "2") (pinfunction "2_2") (pintype "passive"))
      (node (ref "C12") (pin "2") (pinfunction "2_2") (pintype "passive"))
      (node (ref "C13") (pin "2") (pinfunction "2_2") (pintype "passive"))
      (node (ref "C14") (pin "2") (pinfunction "2_2") (pintype "passive"))
      (node (ref "C15") (pin "2") (pinfunction "2_2") (pintype "passive"))
      (node (ref "C16") (pin "2") (pinfunction "2_2") (pintype "passive"))
      (node (ref "C17") (pin "1") (pinfunction "1_1") (pintype "passive"))
      (node (ref "C18\\") (pin "1") (pinfunction "1_1") (pintype "passive"))
      (node (ref "C19") (pin "2") (pinfunction "2_2") (pintype "passive"))
      (node (ref "C2") (pin "1") (pinfunction "1_1") (pintype "passive"))
      (node (ref "C20") (pin "2") (pinfunction "2_2") (pintype "passive"))
      (node (ref "C21") (pin "2") (pinfunction "2_2") (pintype "passive"))
      (node (ref "C22") (pin "2") (pinfunction "2_2") (pintype "passive"))
      (node (ref "C23") (pin "2") (pinfunction "2_2") (pintype "passive"))
      (node (ref "C24") (pin "1") (pinfunction "1_1") (pintype "passive"))
      (node (ref "C25") (pin "2") (pinfunction "2_2") (pintype "passive"))
      (node (ref "C27") (pin "1") (pinfunction "1_1") (pintype "passive"))
      (node (ref "C29") (pin "1") (pinfunction "1_1") (pintype "passive"))
      (node (ref "C3") (pin "2") (pinfunction "2_2") (pintype "passive"))
      (node (ref "C30") (pin "1") (pinfunction "1_1") (pintype "passive"))
      (node (ref "C31") (pin "1") (pinfunction "1_1") (pintype "passive"))
      (node (ref "C32") (pin "1") (pinfunction "1_1") (pintype "passive"))
      (node (ref "C33") (pin "2") (pinfunction "2_2") (pintype "passive"))
      (node (ref "C34") (pin "1") (pinfunction "1_1") (pintype "passive"))
      (node (ref "C37") (pin "1") (pinfunction "1_1") (pintype "passive"))
      (node (ref "C38") (pin "1") (pinfunction "1_1") (pintype "passive"))
      (node (ref "C39") (pin "2") (pinfunction "2_2") (pintype "passive"))
      (node (ref "C4") (pin "2") (pinfunction "2_2") (pintype "passive"))
      (node (ref "C42") (pin "1") (pinfunction "1_1") (pintype "passive"))
      (node (ref "C43") (pin "2") (pinfunction "2_2") (pintype "passive"))
      (node (ref "C5") (pin "2") (pinfunction "2_2") (pintype "passive"))
      (node (ref "C6") (pin "2") (pinfunction "2_2") (pintype "passive"))
      (node (ref "C7") (pin "2") (pinfunction "2_2") (pintype "passive"))
      (node (ref "C8") (pin "2") (pinfunction "2_2") (pintype "passive"))
      (node (ref "C9") (pin "2") (pinfunction "2_2") (pintype "passive"))
      (node (ref "D3") (pin "2") (pinfunction "GND_2") (pintype "bidirectional"))
      (node (ref "D4") (pin "1") (pinfunction "K_1") (pintype "bidirectional"))
      (node (ref "EDP_C1") (pin "1") (pinfunction "1_1") (pintype "passive"))
      (node (ref "EDP_C10") (pin "1") (pinfunction "1_1") (pintype "passive"))
      (node (ref "EDP_C11") (pin "2") (pinfunction "2_2") (pintype "passive"))
      (node (ref "EDP_C12") (pin "2") (pinfunction "2_2") (pintype "passive"))
      (node (ref "EDP_C2") (pin "1") (pinfunction "1_1") (pintype "passive"))
      (node (ref "EDP_C5") (pin "1") (pinfunction "1_1") (pintype "passive"))
      (node (ref "EDP_C6") (pin "1") (pinfunction "1_1") (pintype "passive"))
      (node (ref "EDP_C7") (pin "1") (pinfunction "1_1") (pintype "passive"))
      (node (ref "EDP_C8") (pin "1") (pinfunction "1_1") (pintype "passive"))
      (node (ref "EDP_C9") (pin "1") (pinfunction "1_1") (pintype "passive"))
      (node (ref "IC1") (pin "D2") (pinfunction "GND_D2") (pintype "bidirectional"))
      (node (ref "IC2") (pin "B1") (pinfunction "IN/TRIG_B1") (pintype "bidirectional"))
      (node (ref "IC2") (pin "B3") (pinfunction "GND_B3") (pintype "bidirectional"))
      (node (ref "IC3") (pin "8") (pinfunction "GNDIO_8") (pintype "bidirectional"))
      (node (ref "IC3") (pin "9") (pinfunction "GND_9") (pintype "bidirectional"))
      (node (ref "IC9") (pin "B1") (pinfunction "VSEL_B1") (pintype "bidirectional"))
      (node (ref "IC9") (pin "C1") (pinfunction "AGND_C1") (pintype "bidirectional"))
      (node (ref "IC9") (pin "C2") (pinfunction "PGND_1_C2") (pintype "bidirectional"))
      (node (ref "IC9") (pin "C3") (pinfunction "PGND_2_C3") (pintype "bidirectional"))
      (node (ref "J1") (pin "3") (pinfunction "3_3") (pintype "bidirectional"))
      (node (ref "J1") (pin "5") (pinfunction "5_5") (pintype "bidirectional"))
      (node (ref "J2") (pin "17") (pinfunction "17_17") (pintype "bidirectional"))
      (node (ref "J2") (pin "8") (pinfunction "8_8") (pintype "bidirectional"))
      (node (ref "J2") (pin "MP1") (pinfunction "MP1_MP1") (pintype "bidirectional"))
      (node (ref "J2") (pin "MP2") (pinfunction "MP2_MP2") (pintype "bidirectional"))
      (node (ref "J4") (pin "A12_B1") (pinfunction "GND_A12_B1") (pintype "power_in"))
      (node (ref "J4") (pin "A1_B12") (pinfunction "GND_A1_B12") (pintype "power_in"))
      (node (ref "J4") (pin "SH1") (pinfunction "SHIELD_SH1") (pintype "passive"))
      (node (ref "J4") (pin "SH2") (pinfunction "SHIELD_SH2") (pintype "passive"))
      (node (ref "J4") (pin "SH3") (pinfunction "SHIELD_SH3") (pintype "passive"))
      (node (ref "J4") (pin "SH4") (pinfunction "SHIELD_SH4") (pintype "passive"))
      (node (ref "R1_USB") (pin "1") (pinfunction "1_1") (pintype "bidirectional"))
      (node (ref "R2_EP_DR") (pin "2") (pinfunction "2_2") (pintype "bidirectional"))
      (node (ref "R2_USB") (pin "2") (pinfunction "2_2") (pintype "bidirectional"))
      (node (ref "R3") (pin "1") (pinfunction "1_1") (pintype "bidirectional"))
      (node (ref "R9") (pin "1") (pinfunction "1_1") (pintype "bidirectional"))
      (node (ref "R_TYPE_SEL") (pin "2") (pinfunction "2_2") (pintype "bidirectional"))
      (node (ref "SJ1") (pin "1") (pinfunction "1_1") (pintype "passive"))
      (node (ref "SW_DN") (pin "1") (pinfunction "1_1") (pintype "passive"))
      (node (ref "SW_ENT") (pin "1") (pinfunction "1_1") (pintype "passive"))
      (node (ref "SW_UP") (pin "1") (pinfunction "1_1") (pintype "passive"))
      (node (ref "TP_BAT_GND") (pin "TP") (pinfunction "TP_TP") (pintype "input"))
      (node (ref "TP_GND") (pin "TP") (pinfunction "TP_TP") (pintype "input"))
      (node (ref "U1") (pin "P$74") (pinfunction "VSS_PAD_P$74") (pintype "bidirectional"))
      (node (ref "U1") (pin "P$75") (pinfunction "VSS_PAD_P$75") (pintype "bidirectional"))
      (node (ref "U1") (pin "P$76") (pinfunction "VSS_PAD_P$76") (pintype "bidirectional"))
      (node (ref "U1") (pin "P$77") (pinfunction "VSS_PAD_P$77") (pintype "bidirectional"))
      (node (ref "U1") (pin "P$78") (pinfunction "VSS_PAD_P$78") (pintype "bidirectional"))
      (node (ref "U1") (pin "P$79") (pinfunction "VSS_PAD_P$79") (pintype "bidirectional"))
      (node (ref "U1") (pin "P$80") (pinfunction "VSS_PAD_P$80") (pintype "bidirectional"))
      (node (ref "U1") (pin "P$81") (pinfunction "VSS_PAD_P$81") (pintype "bidirectional"))
      (node (ref "U1") (pin "P$82") (pinfunction "VSS_PAD_P$82") (pintype "bidirectional"))
      (node (ref "U1") (pin "P$83") (pinfunction "VSS_PAD_P$83") (pintype "bidirectional"))
      (node (ref "U1") (pin "P$84") (pinfunction "VSS_PAD_P$84") (pintype "bidirectional"))
      (node (ref "U1") (pin "P$85") (pinfunction "VSS_PAD_P$85") (pintype "bidirectional"))
      (node (ref "U1") (pin "P$86") (pinfunction "VSS_PAD_P$86") (pintype "bidirectional"))
      (node (ref "U1") (pin "P$87") (pinfunction "VSS_PAD_P$87") (pintype "bidirectional"))
      (node (ref "U1") (pin "P$88") (pinfunction "VSS_PAD_P$88") (pintype "bidirectional"))
      (node (ref "U1") (pin "P$89") (pinfunction "VSS_PAD_P$89") (pintype "bidirectional"))
      (node (ref "U1") (pin "P$90") (pinfunction "VSS_PAD_P$90") (pintype "bidirectional"))
      (node (ref "U1") (pin "P$B7") (pinfunction "VSS_P$B7") (pintype "power_in"))
      (node (ref "U1") (pin "P$F23") (pinfunction "VSS_PA_P$F23") (pintype "bidirectional"))
      (node (ref "U2") (pin "1") (pinfunction "CTG_1") (pintype "power_in"))
      (node (ref "U2") (pin "4") (pinfunction "GND_4") (pintype "power_in"))
      (node (ref "U2") (pin "6") (pinfunction "QSTRT_6") (pintype "input"))
      (node (ref "U2") (pin "9") (pinfunction "EP_9") (pintype "power_in"))
      (node (ref "X1") (pin "2") (pinfunction "2_2") (pintype "passive"))
      (node (ref "X1") (pin "4") (pinfunction "4_4") (pintype "passive"))
    )
    (net (code "14") (name "HAPTIC_EN") (class "Default")
      (node (ref "IC2") (pin "A1") (pinfunction "EN_A1") (pintype "bidirectional"))
      (node (ref "U1") (pin "P$U1") (pinfunction "P0.12_P$U1") (pintype "bidirectional"))
    )
    (net (code "15") (name "IMU_INT1") (class "Default")
      (node (ref "IC3") (pin "5") (pinfunction "INT1_5") (pintype "bidirectional"))
      (node (ref "U1") (pin "P$N1") (pinfunction "P0.08_P$N1") (pintype "bidirectional"))
    )
    (net (code "16") (name "IMU_INT2") (class "Default")
      (node (ref "IC3") (pin "6") (pinfunction "INT2_6") (pintype "bidirectional"))
      (node (ref "U1") (pin "P$P2") (pinfunction "P1.08_P$P2") (pintype "bidirectional"))
    )
    (net (code "17") (name "LX1") (class "Default")
      (node (ref "IC9") (pin "B2") (pinfunction "SW1_1_B2") (pintype "bidirectional"))
      (node (ref "IC9") (pin "B3") (pinfunction "SW1_2_B3") (pintype "bidirectional"))
      (node (ref "L7") (pin "1") (pinfunction "1_1") (pintype "bidirectional"))
    )
    (net (code "18") (name "LX2") (class "Default")
      (node (ref "IC9") (pin "D2") (pinfunction "SW2_1_D2") (pintype "bidirectional"))
      (node (ref "IC9") (pin "D3") (pinfunction "SW2_2_D3") (pintype "bidirectional"))
      (node (ref "L7") (pin "2") (pinfunction "2_2") (pintype "bidirectional"))
    )
    (net (code "19") (name "MOSI") (class "Default")
      (node (ref "J2") (pin "14") (pinfunction "14_14") (pintype "bidirectional"))
      (node (ref "U1") (pin "P$B13") (pinfunction "P0.03/AIN1_P$B13") (pintype "bidirectional"))
    )
    (net (code "20") (name "Net-(ANT1-FEED)") (class "Default")
      (node (ref "ANT1") (pin "1") (pinfunction "FEED_1") (pintype "input"))
      (node (ref "C22") (pin "1") (pinfunction "1_1") (pintype "passive"))
      (node (ref "C4") (pin "1") (pinfunction "1_1") (pintype "passive"))
      (node (ref "L1") (pin "2") (pinfunction "2_2") (pintype "passive"))
    )
    (net (code "21") (name "Net-(D2-K)") (class "Default")
      (node (ref "C2-EP-DR") (pin "1") (pinfunction "1_1") (pintype "passive"))
      (node (ref "D2") (pin "1") (pinfunction "K_1") (pintype "bidirectional"))
      (node (ref "D4") (pin "2") (pinfunction "A_2") (pintype "bidirectional"))
    )
    (net (code "22") (name "Net-(D5-A)") (class "Default")
      (node (ref "C2-EP-DR") (pin "2") (pinfunction "2_2") (pintype "passive"))
      (node (ref "D5") (pin "2") (pinfunction "A_2") (pintype "bidirectional"))
      (node (ref "L5") (pin "1") (pinfunction "1_1") (pintype "passive"))
      (node (ref "Q3") (pin "3") (pinfunction "D_3") (pintype "bidirectional"))
    )
    (net (code "23") (name "Net-(EDP_C1-Pad2)") (class "Default")
      (node (ref "EDP_C1") (pin "2") (pinfunction "2_2") (pintype "passive"))
      (node (ref "J2") (pin "5") (pinfunction "5_5") (pintype "bidirectional"))
    )
    (net (code "24") (name "Net-(EDP_C2-Pad2)") (class "Default")
      (node (ref "EDP_C2") (pin "2") (pinfunction "2_2") (pintype "passive"))
      (node (ref "J2") (pin "4") (pinfunction "4_4") (pintype "bidirectional"))
    )
    (net (code "25") (name "Net-(EDP_C6-Pad2)") (class "Default")
      (node (ref "EDP_C6") (pin "2") (pinfunction "2_2") (pintype "passive"))
      (node (ref "J2") (pin "18") (pinfunction "18_18") (pintype "bidirectional"))
    )
    (net (code "26") (name "Net-(EDP_C7-Pad2)") (class "Default")
      (node (ref "EDP_C7") (pin "2") (pinfunction "2_2") (pintype "passive"))
      (node (ref "J2") (pin "19") (pinfunction "19_19") (pintype "bidirectional"))
    )
    (net (code "27") (name "Net-(EDP_C8-Pad2)") (class "Default")
      (node (ref "EDP_C8") (pin "2") (pinfunction "2_2") (pintype "passive"))
      (node (ref "J2") (pin "20") (pinfunction "20_20") (pintype "bidirectional"))
    )
    (net (code "28") (name "Net-(EDP_C10-Pad2)") (class "Default")
      (node (ref "EDP_C10") (pin "2") (pinfunction "2_2") (pintype "passive"))
      (node (ref "J2") (pin "22") (pinfunction "22_22") (pintype "bidirectional"))
    )
    (net (code "29") (name "Net-(EDP_C12-Pad1)") (class "Default")
      (node (ref "EDP_C12") (pin "1") (pinfunction "1_1") (pintype "passive"))
      (node (ref "J2") (pin "24") (pinfunction "24_24") (pintype "bidirectional"))
    )
    (net (code "30") (name "Net-(IC1-TS{slash}MR)") (class "Default")
      (node (ref "IC1") (pin "D1") (pinfunction "TS/MR_D1") (pintype "bidirectional"))
      (node (ref "R9") (pin "2") (pinfunction "2_2") (pintype "bidirectional"))
    )
    (net (code "31") (name "Net-(IC2-REG)") (class "Default")
      (node (ref "C32") (pin "2") (pinfunction "2_2") (pintype "passive"))
      (node (ref "IC2") (pin "A2") (pinfunction "REG_A2") (pintype "bidirectional"))
    )
    (net (code "32") (name "Net-(IC3-SDO)") (class "Default")
      (node (ref "IC3") (pin "1") (pinfunction "SDO_1") (pintype "bidirectional"))
      (node (ref "R3") (pin "2") (pinfunction "2_2") (pintype "bidirectional"))
    )
    (net (code "33") (name "Net-(IC9-SCL)") (class "Default")
      (node (ref "IC9") (pin "D1") (pinfunction "SCL_D1") (pintype "bidirectional"))
      (node (ref "R1") (pin "2") (pinfunction "2_2") (pintype "bidirectional"))
    )
    (net (code "34") (name "Net-(IC9-SDA)") (class "Default")
      (node (ref "IC9") (pin "E1") (pinfunction "SDA_E1") (pintype "bidirectional"))
      (node (ref "R2") (pin "2") (pinfunction "2_2") (pintype "bidirectional"))
    )
    (net (code "35") (name "Net-(J4-CC1)") (class "Default")
      (node (ref "J4") (pin "A5") (pinfunction "CC1_A5") (pintype "bidirectional"))
      (node (ref "R1_USB") (pin "2") (pinfunction "2_2") (pintype "bidirectional"))
    )
    (net (code "36") (name "Net-(J4-CC2)") (class "Default")
      (node (ref "J4") (pin "B5") (pinfunction "CC2_B5") (pintype "bidirectional"))
      (node (ref "R2_USB") (pin "1") (pinfunction "1_1") (pintype "bidirectional"))
    )
    (net (code "37") (name "Net-(L2-Pad2)") (class "Default")
      (node (ref "L2") (pin "2") (pinfunction "2_2") (pintype "passive"))
      (node (ref "L3\\") (pin "1") (pinfunction "1_1") (pintype "passive"))
    )
    (net (code "38") (name "Net-(R1_EP_DR1-Pad2)") (class "Default")
      (node (ref "R1_EP_DR1") (pin "2") (pinfunction "2_2") (pintype "bidirectional"))
      (node (ref "R_TYPE_SEL") (pin "1") (pinfunction "1_1") (pintype "bidirectional"))
      (node (ref "SJ1") (pin "2") (pinfunction "2_2") (pintype "passive"))
    )
    (net (code "39") (name "Net-(U1-ANT)") (class "Default")
      (node (ref "C3") (pin "1") (pinfunction "1_1") (pintype "passive"))
      (node (ref "L1") (pin "1") (pinfunction "1_1") (pintype "passive"))
      (node (ref "U1") (pin "P$H23") (pinfunction "ANT_P$H23") (pintype "bidirectional"))
    )
    (net (code "40") (name "Net-(U1-DCC)") (class "Default")
      (node (ref "L2") (pin "1") (pinfunction "1_1") (pintype "passive"))
      (node (ref "U1") (pin "P$B3") (pinfunction "DCC_P$B3") (pintype "output"))
    )
    (net (code "41") (name "Net-(U1-DEC1)") (class "Default")
      (node (ref "C5") (pin "1") (pinfunction "1_1") (pintype "passive"))
      (node (ref "U1") (pin "P$C1") (pinfunction "DEC1_P$C1") (pintype "power_in"))
    )
    (net (code "42") (name "Net-(U1-DEC2)") (class "Default")
      (node (ref "C13") (pin "1") (pinfunction "1_1") (pintype "passive"))
      (node (ref "U1") (pin "P$A18") (pinfunction "DEC2_P$A18") (pintype "bidirectional"))
    )
    (net (code "43") (name "Net-(U1-DEC3)") (class "Default")
      (node (ref "C11") (pin "1") (pinfunction "1_1") (pintype "passive"))
      (node (ref "U1") (pin "P$D23") (pinfunction "DEC3_P$D23") (pintype "bidirectional"))
    )
    (net (code "44") (name "Net-(U1-DEC3V3)") (class "Default")
      (node (ref "C20") (pin "1") (pinfunction "1_1") (pintype "passive"))
      (node (ref "U1") (pin "P$AC5") (pinfunction "DEC3V3_P$AC5") (pintype "bidirectional"))
    )
    (net (code "45") (name "Net-(U1-DEC4)") (class "Default")
      (node (ref "C10") (pin "1") (pinfunction "1_1") (pintype "passive"))
      (node (ref "C15") (pin "1") (pinfunction "1_1") (pintype "passive"))
      (node (ref "C16") (pin "1") (pinfunction "1_1") (pintype "passive"))
      (node (ref "L3\\") (pin "2") (pinfunction "2_2") (pintype "passive"))
      (node (ref "U1") (pin "P$B5") (pinfunction "DEC4_P$B5") (pintype "power_in"))
      (node (ref "U1") (pin "P$E24") (pinfunction "DEC6_P$E24") (pintype "bidirectional"))
    )
    (net (code "46") (name "Net-(U1-DEC5)") (class "Default")
      (node (ref "C9") (pin "1") (pinfunction "1_1") (pintype "passive"))
      (node (ref "U1") (pin "P$N24") (pinfunction "DEC5_P$N24") (pintype "bidirectional"))
    )
    (net (code "47") (name "Net-(U1-P0.00{slash}XL1)") (class "Default")
      (node (ref "C17") (pin "2") (pinfunction "2_2") (pintype "passive"))
      (node (ref "U1") (pin "P$D2") (pinfunction "P0.00/XL1_P$D2") (pintype "bidirectional"))
      (node (ref "X2") (pin "2") (pinfunction "2_2") (pintype "passive"))
    )
    (net (code "48") (name "Net-(U1-P0.01{slash}XL2)") (class "Default")
      (node (ref "C18\\") (pin "2") (pinfunction "2_2") (pintype "passive"))
      (node (ref "U1") (pin "P$F2") (pinfunction "P0.01/XL2_P$F2") (pintype "bidirectional"))
      (node (ref "X2") (pin "1") (pinfunction "1_1") (pintype "passive"))
    )
    (net (code "49") (name "Net-(U1-XC1)") (class "Default")
      (node (ref "C1") (pin "1") (pinfunction "1_1") (pintype "passive"))
      (node (ref "U1") (pin "P$B24") (pinfunction "XC1_P$B24") (pintype "input"))
      (node (ref "X1") (pin "1") (pinfunction "1_1") (pintype "passive"))
    )
    (net (code "50") (name "Net-(U1-XC2)") (class "Default")
      (node (ref "C2") (pin "2") (pinfunction "2_2") (pintype "passive"))
      (node (ref "U1") (pin "P$A23") (pinfunction "XC2_P$A23") (pintype "output"))
      (node (ref "X1") (pin "3") (pinfunction "3_3") (pintype "passive"))
    )
    (net (code "51") (name "OUT+") (class "Default")
      (node (ref "IC2") (pin "A3") (pinfunction "OUT+_A3") (pintype "bidirectional"))
      (node (ref "TP_OP") (pin "TP") (pinfunction "TP_TP") (pintype "input"))
    )
    (net (code "52") (name "OUT-") (class "Default")
      (node (ref "IC2") (pin "C3") (pinfunction "OUT-_C3") (pintype "bidirectional"))
      (node (ref "TP_ON") (pin "TP") (pinfunction "TP_TP") (pintype "input"))
    )
    (net (code "53") (name "P0.04") (class "Default")
      (node (ref "U1") (pin "P$J1") (pinfunction "P0.04/AIN2_P$J1") (pintype "bidirectional"))
    )
    (net (code "54") (name "P0.09") (class "Default")
      (node (ref "U1") (pin "P$L24") (pinfunction "P0.09/NFC1_P$L24") (pintype "bidirectional"))
    )
    (net (code "55") (name "P0.13") (class "Default")
      (node (ref "C30") (pin "2") (pinfunction "2_2") (pintype "passive"))
      (node (ref "R5") (pin "2") (pinfunction "2_2") (pintype "bidirectional"))
      (node (ref "SW_UP") (pin "2") (pinfunction "2_2") (pintype "passive"))
      (node (ref "U1") (pin "P$AD8") (pinfunction "P0.13_P$AD8") (pintype "bidirectional"))
    )
    (net (code "56") (name "P0.14") (class "Default")
      (node (ref "C31") (pin "2") (pinfunction "2_2") (pintype "passive"))
      (node (ref "R8") (pin "2") (pinfunction "2_2") (pintype "bidirectional"))
      (node (ref "SW_ENT") (pin "2") (pinfunction "2_2") (pintype "passive"))
      (node (ref "U1") (pin "P$AC9") (pinfunction "P0.14_P$AC9") (pintype "bidirectional"))
    )
    (net (code "57") (name "P0.19") (class "Default")
      (node (ref "U1") (pin "P$AC15") (pinfunction "P0.19_P$AC15") (pintype "bidirectional"))
    )
    (net (code "58") (name "P0.20") (class "Default")
      (node (ref "U1") (pin "P$AD16") (pinfunction "P0.20_P$AD16") (pintype "bidirectional"))
    )
    (net (code "59") (name "P0.21") (class "Default")
      (node (ref "U1") (pin "P$AC17") (pinfunction "P0.21_P$AC17") (pintype "bidirectional"))
    )
    (net (code "60") (name "P0.22") (class "Default")
      (node (ref "U1") (pin "P$AD18") (pinfunction "P0.22_P$AD18") (pintype "bidirectional"))
    )
    (net (code "61") (name "P0.23") (class "Default")
      (node (ref "U1") (pin "P$AC19") (pinfunction "P0.23_P$AC19") (pintype "bidirectional"))
    )
    (net (code "62") (name "P0.24") (class "Default")
      (node (ref "U1") (pin "P$AD20") (pinfunction "P0.24_P$AD20") (pintype "bidirectional"))
    )
    (net (code "63") (name "P0.25") (class "Default")
      (node (ref "U1") (pin "P$AC21") (pinfunction "P0.25_P$AC21") (pintype "bidirectional"))
    )
    (net (code "64") (name "P0.26") (class "Default")
      (node (ref "U1") (pin "P$G1") (pinfunction "P0.26_P$G1") (pintype "bidirectional"))
    )
    (net (code "65") (name "P0.27") (class "Default")
      (node (ref "U1") (pin "P$H2") (pinfunction "P0.27_P$H2") (pintype "bidirectional"))
    )
    (net (code "66") (name "P0.28") (class "Default")
      (node (ref "U1") (pin "P$B11") (pinfunction "P0.28/AIN4_P$B11") (pintype "bidirectional"))
    )
    (net (code "67") (name "P0.29") (class "Default")
      (node (ref "U1") (pin "P$A10") (pinfunction "P0.29/AIN5_P$A10") (pintype "bidirectional"))
    )
    (net (code "68") (name "P0.30") (class "Default")
      (node (ref "U1") (pin "P$B9") (pinfunction "P0.30/AIN6_P$B9") (pintype "bidirectional"))
    )
    (net (code "69") (name "P0.31") (class "Default")
      (node (ref "U1") (pin "P$A8") (pinfunction "P0.31/AIN7_P$A8") (pintype "bidirectional"))
    )
    (net (code "70") (name "P1.01") (class "Default")
      (node (ref "Q1") (pin "1") (pinfunction "G_1") (pintype "bidirectional"))
      (node (ref "R_PWR_EPD") (pin "2") (pinfunction "2_2") (pintype "bidirectional"))
      (node (ref "U1") (pin "P$Y23") (pinfunction "P1.01_P$Y23") (pintype "bidirectional"))
    )
    (net (code "71") (name "P1.02") (class "Default")
      (node (ref "C29") (pin "2") (pinfunction "2_2") (pintype "passive"))
      (node (ref "R7") (pin "2") (pinfunction "2_2") (pintype "bidirectional"))
      (node (ref "SW_DN") (pin "2") (pinfunction "2_2") (pintype "passive"))
      (node (ref "U1") (pin "P$W24") (pinfunction "P1.02_P$W24") (pintype "bidirectional"))
    )
    (net (code "72") (name "P1.03") (class "Default")
      (node (ref "U1") (pin "P$V23") (pinfunction "P1.03_P$V23") (pintype "bidirectional"))
    )
    (net (code "73") (name "P1.04") (class "Default")
      (node (ref "U1") (pin "P$U24") (pinfunction "P1.04_P$U24") (pintype "bidirectional"))
    )
    (net (code "74") (name "P1.05") (class "Default")
      (node (ref "U1") (pin "P$T23") (pinfunction "P1.05_P$T23") (pintype "bidirectional"))
    )
    (net (code "75") (name "P1.06") (class "Default")
      (node (ref "U1") (pin "P$R24") (pinfunction "P1.06_P$R24") (pintype "bidirectional"))
    )
    (net (code "76") (name "P1.07") (class "Default")
      (node (ref "U1") (pin "P$P23") (pinfunction "P1.07_P$P23") (pintype "bidirectional"))
    )
    (net (code "77") (name "P1.09") (class "Default")
      (node (ref "U1") (pin "P$R1") (pinfunction "P1.09_P$R1") (pintype "bidirectional"))
    )
    (net (code "78") (name "P1.10") (class "Default")
      (node (ref "U1") (pin "P$A20") (pinfunction "P1.10_P$A20") (pintype "bidirectional"))
    )
    (net (code "79") (name "P1.11") (class "Default")
      (node (ref "U1") (pin "P$B19") (pinfunction "P1.11_P$B19") (pintype "bidirectional"))
    )
    (net (code "80") (name "P1.12") (class "Default")
      (node (ref "U1") (pin "P$B17") (pinfunction "P1.12_P$B17") (pintype "bidirectional"))
    )
    (net (code "81") (name "P1.13") (class "Default")
      (node (ref "U1") (pin "P$A16") (pinfunction "P1.13_P$A16") (pintype "bidirectional"))
    )
    (net (code "82") (name "P1.14") (class "Default")
      (node (ref "U1") (pin "P$B15") (pinfunction "P1.14_P$B15") (pintype "bidirectional"))
    )
    (net (code "83") (name "P1.15") (class "Default")
      (node (ref "U1") (pin "P$A14") (pinfunction "P1.15_P$A14") (pintype "bidirectional"))
    )
    (net (code "84") (name "PMIC_INT") (class "Default")
      (node (ref "IC1") (pin "A1") (pinfunction "~{INT}_A1") (pintype "bidirectional"))
      (node (ref "U1") (pin "P$T2") (pinfunction "P0.11_P$T2") (pintype "bidirectional"))
    )
    (net (code "85") (name "PREVGH") (class "Default")
      (node (ref "D5") (pin "1") (pinfunction "K_1") (pintype "bidirectional"))
      (node (ref "EDP_C9") (pin "2") (pinfunction "2_2") (pintype "passive"))
      (node (ref "J2") (pin "21") (pinfunction "21_21") (pintype "bidirectional"))
    )
    (net (code "86") (name "PREVGL") (class "Default")
      (node (ref "D2") (pin "2") (pinfunction "A_2") (pintype "bidirectional"))
      (node (ref "EDP_C11") (pin "1") (pinfunction "1_1") (pintype "passive"))
      (node (ref "J2") (pin "23") (pinfunction "23_23") (pintype "bidirectional"))
    )
    (net (code "87") (name "RESE") (class "Default")
      (node (ref "J2") (pin "3") (pinfunction "3_3") (pintype "bidirectional"))
      (node (ref "Q3") (pin "2") (pinfunction "S_2") (pintype "bidirectional"))
      (node (ref "R1_EP_DR1") (pin "1") (pinfunction "1_1") (pintype "bidirectional"))
    )
    (net (code "88") (name "RESET") (class "Default")
      (node (ref "J1") (pin "6") (pinfunction "6_6") (pintype "bidirectional"))
      (node (ref "TP_RESET") (pin "TP") (pinfunction "TP_TP") (pintype "input"))
      (node (ref "U1") (pin "P$AC13") (pinfunction "P0.18/RESET_P$AC13") (pintype "bidirectional"))
    )
    (net (code "89") (name "SCK") (class "Default")
      (node (ref "J2") (pin "13") (pinfunction "13_13") (pintype "bidirectional"))
      (node (ref "U1") (pin "P$A12") (pinfunction "P0.02/AIN0_P$A12") (pintype "bidirectional"))
    )
    (net (code "90") (name "SCL") (class "Default")
      (node (ref "IC1") (pin "B1") (pinfunction "SCL_B1") (pintype "bidirectional"))
      (node (ref "IC2") (pin "C1") (pinfunction "SCL_C1") (pintype "bidirectional"))
      (node (ref "IC3") (pin "12") (pinfunction "SCX_12") (pintype "bidirectional"))
      (node (ref "R1") (pin "1") (pinfunction "1_1") (pintype "bidirectional"))
      (node (ref "R17") (pin "1") (pinfunction "1_1") (pintype "bidirectional"))
      (node (ref "TP_SCL") (pin "TP") (pinfunction "TP_TP") (pintype "input"))
      (node (ref "U1") (pin "P$M2") (pinfunction "P0.07_P$M2") (pintype "bidirectional"))
      (node (ref "U2") (pin "7") (pinfunction "SCL_7") (pintype "input"))
    )
    (net (code "91") (name "SDA") (class "Default")
      (node (ref "IC1") (pin "C1") (pinfunction "SDA_C1") (pintype "bidirectional"))
      (node (ref "IC2") (pin "B2") (pinfunction "SDA_B2") (pintype "bidirectional"))
      (node (ref "IC3") (pin "2") (pinfunction "SDX_2") (pintype "bidirectional"))
      (node (ref "R18") (pin "1") (pinfunction "1_1") (pintype "bidirectional"))
      (node (ref "R2") (pin "1") (pinfunction "1_1") (pintype "bidirectional"))
      (node (ref "TP_SDA") (pin "TP") (pinfunction "TP_TP") (pintype "input"))
      (node (ref "U1") (pin "P$L1") (pinfunction "P0.06_P$L1") (pintype "bidirectional"))
      (node (ref "U2") (pin "8") (pinfunction "SDA_8") (pintype "bidirectional"))
    )
    (net (code "92") (name "SWDCLK") (class "Default")
      (node (ref "J1") (pin "4") (pinfunction "4_4") (pintype "bidirectional"))
      (node (ref "TP_SWDCLK") (pin "TP") (pinfunction "TP_TP") (pintype "input"))
      (node (ref "U1") (pin "P$AA24") (pinfunction "SWDCLK_P$AA24") (pintype "input"))
    )
    (net (code "93") (name "SWDIO") (class "Default")
      (node (ref "J1") (pin "2") (pinfunction "2_2") (pintype "bidirectional"))
      (node (ref "TP_SWDIO") (pin "TP") (pinfunction "TP_TP") (pintype "input"))
      (node (ref "U1") (pin "P$AC24") (pinfunction "SWDIO_P$AC24") (pintype "bidirectional"))
    )
    (net (code "94") (name "SWO") (class "Default")
      (node (ref "TP_SWO") (pin "TP") (pinfunction "TP_TP") (pintype "input"))
      (node (ref "U1") (pin "P$AD22") (pinfunction "P1.00_P$AD22") (pintype "bidirectional"))
    )
    (net (code "95") (name "VBAT") (class "Default")
      (node (ref "C27") (pin "2") (pinfunction "2_2") (pintype "passive"))
      (node (ref "C37") (pin "2") (pinfunction "2_2") (pintype "passive"))
      (node (ref "IC1") (pin "C2") (pinfunction "BAT_C2") (pintype "bidirectional"))
      (node (ref "TP_VBAT") (pin "TP") (pinfunction "TP_TP") (pintype "input"))
      (node (ref "U2") (pin "2") (pinfunction "CELL_2") (pintype "power_in"))
      (node (ref "U2") (pin "3") (pinfunction "VDD_3") (pintype "power_in"))
    )
    (net (code "96") (name "VBUS") (class "Default")
      (node (ref "C21") (pin "1") (pinfunction "1_1") (pintype "passive"))
      (node (ref "C38") (pin "2") (pinfunction "2_2") (pintype "passive"))
      (node (ref "C42") (pin "2") (pinfunction "2_2") (pintype "passive"))
      (node (ref "C43") (pin "1") (pinfunction "1_1") (pintype "passive"))
      (node (ref "D3") (pin "5") (pinfunction "VBUS_5") (pintype "bidirectional"))
      (node (ref "IC1") (pin "A2") (pinfunction "IN_A2") (pintype "bidirectional"))
      (node (ref "J4") (pin "A4_B9") (pinfunction "VBUS_A4_B9") (pintype "power_in"))
      (node (ref "J4") (pin "A9_B4") (pinfunction "VBUS_A9_B4") (pintype "power_in"))
      (node (ref "U1") (pin "P$AD2") (pinfunction "VBUS_P$AD2") (pintype "power_in"))
    )
    (net (code "97") (name "VREG") (class "Default")
      (node (ref "C23") (pin "1") (pinfunction "1_1") (pintype "passive"))
      (node (ref "C24") (pin "2") (pinfunction "2_2") (pintype "passive"))
      (node (ref "C39") (pin "1") (pinfunction "1_1") (pintype "passive"))
      (node (ref "IC1") (pin "B2") (pinfunction "SYS_B2") (pintype "bidirectional"))
      (node (ref "IC9") (pin "A1") (pinfunction "EN_A1") (pintype "bidirectional"))
      (node (ref "IC9") (pin "A2") (pinfunction "VIN_1_A2") (pintype "bidirectional"))
      (node (ref "IC9") (pin "A3") (pinfunction "VIN_2_A3") (pintype "bidirectional"))
      (node (ref "TP_VREG") (pin "TP") (pinfunction "TP_TP") (pintype "input"))
    )
    (net (code "98") (name "unconnected-(ANT1-NC-Pad2)") (class "Default")
      (node (ref "ANT1") (pin "2") (pinfunction "NC_2") (pintype "no_connect"))
    )
    (net (code "99") (name "unconnected-(IC3-ASCL-Pad11)") (class "Default")
      (node (ref "IC3") (pin "11") (pinfunction "ASCL_11") (pintype "bidirectional"))
    )
    (net (code "100") (name "unconnected-(IC3-ASDA-Pad4)") (class "Default")
      (node (ref "IC3") (pin "4") (pinfunction "ASDA_4") (pintype "bidirectional"))
    )
    (net (code "101") (name "unconnected-(J2-Pad1)") (class "Default")
      (node (ref "J2") (pin "1") (pinfunction "1_1") (pintype "bidirectional"))
    )
    (net (code "102") (name "unconnected-(J2-Pad6)") (class "Default")
      (node (ref "J2") (pin "6") (pinfunction "6_6") (pintype "bidirectional"))
    )
    (net (code "103") (name "unconnected-(J2-Pad7)") (class "Default")
      (node (ref "J2") (pin "7") (pinfunction "7_7") (pintype "bidirectional"))
    )
    (net (code "104") (name "unconnected-(J4-SBU1-PadA8)") (class "Default")
      (node (ref "J4") (pin "A8") (pinfunction "SBU1_A8") (pintype "bidirectional"))
    )
    (net (code "105") (name "unconnected-(J4-SBU2-PadB8)") (class "Default")
      (node (ref "J4") (pin "B8") (pinfunction "SBU2_B8") (pintype "bidirectional"))
    )
    (net (code "106") (name "unconnected-(U1-DCCH-PadP$AB2)") (class "Default")
      (node (ref "U1") (pin "P$AB2") (pinfunction "DCCH_P$AB2") (pintype "bidirectional"))
    )
  )
)
